# test_2620.net
KiCad netlist of a schematic drawn in EAGLE
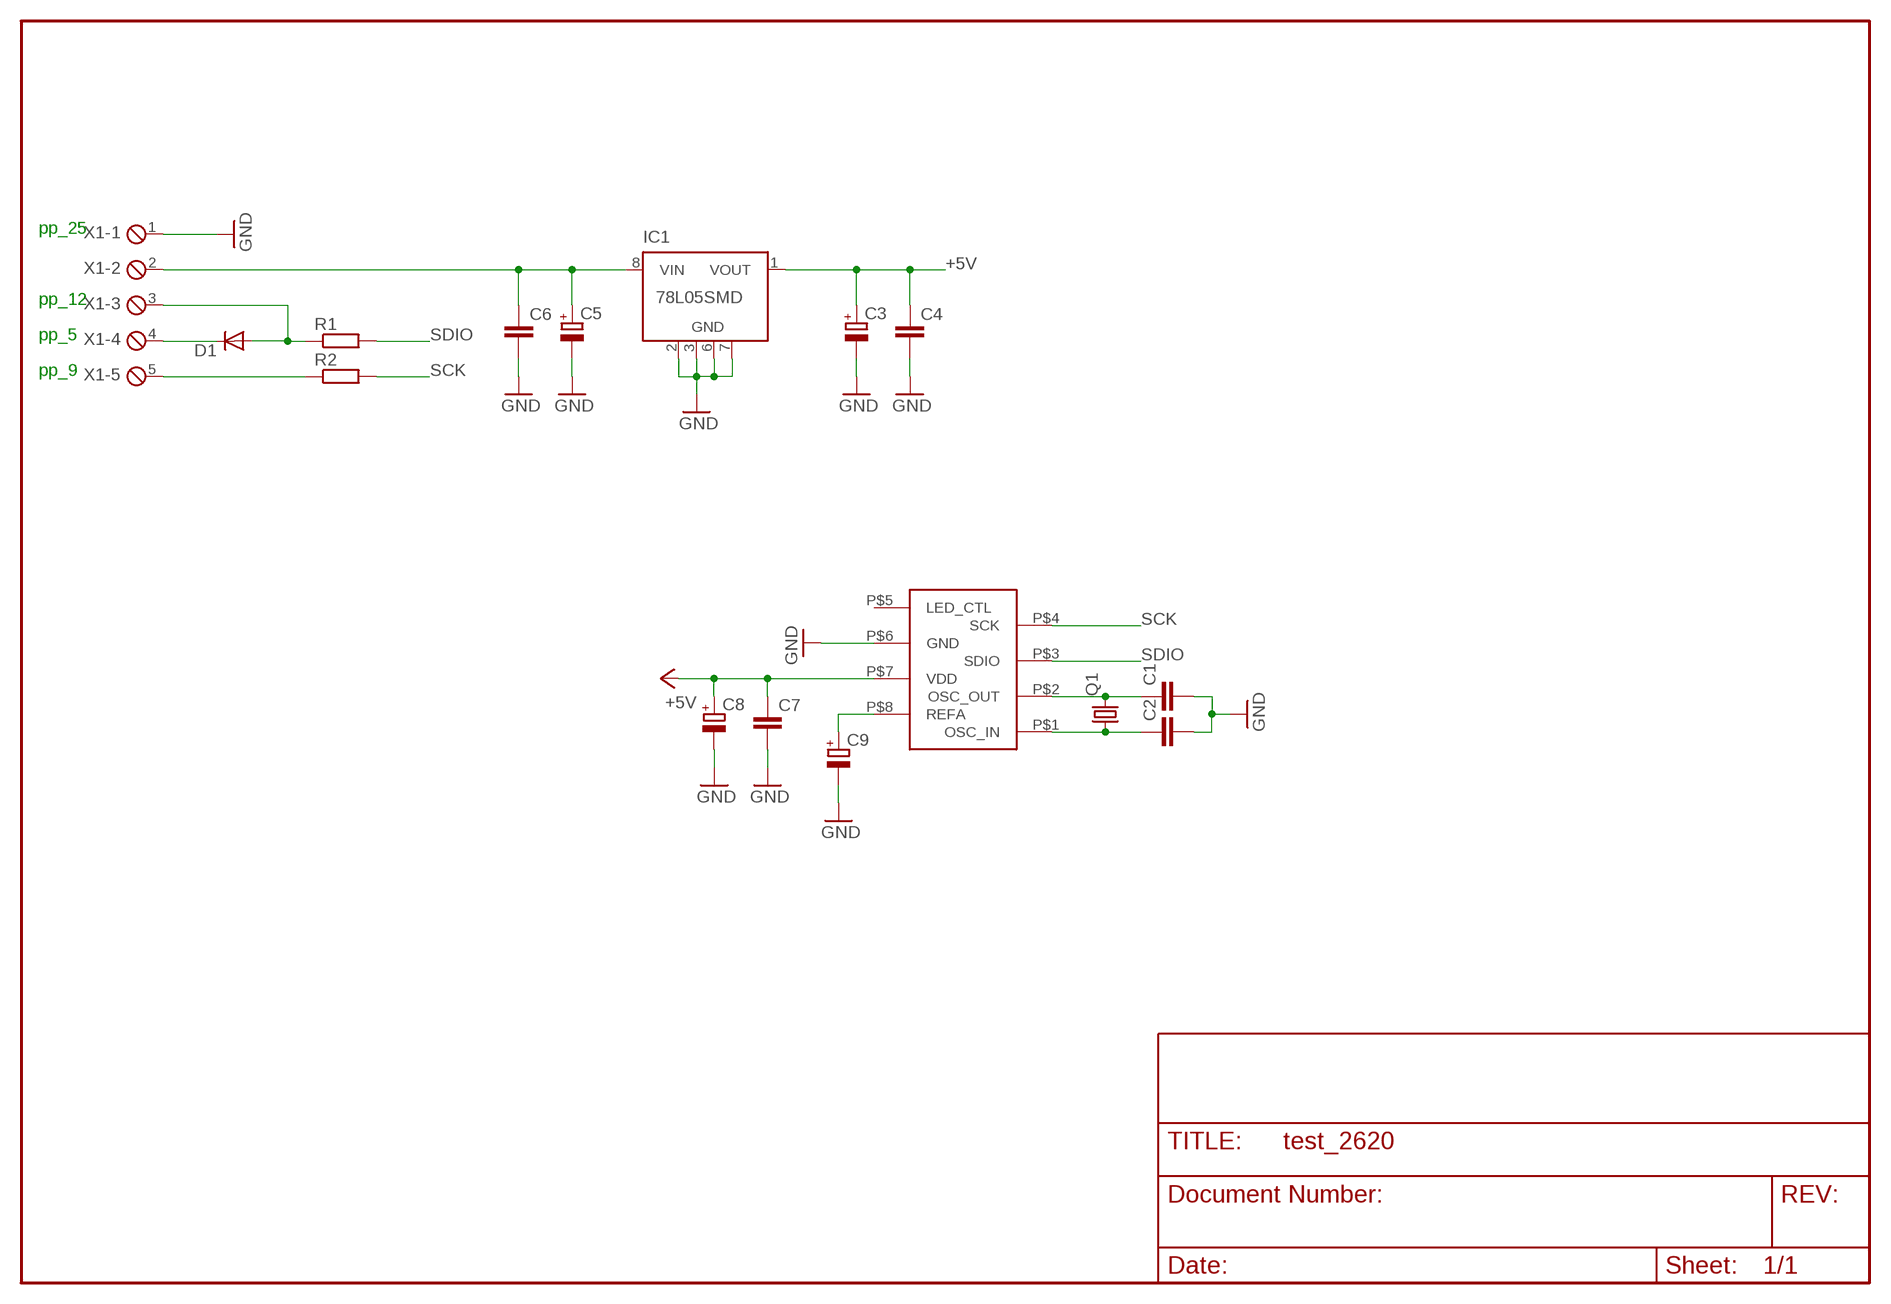
[diagram p0: schematic, sheet 1]

(export (version "E")
  (design (tool "Eeschema 10.0.6"))
  (components
    (comp (ref "C1")
      (value "C-EUC0805K")
      (footprint "eagle-import:C0805K")
      (libsource (lib "eagle-import") (part "C-EUC0805K"))
    )
    (comp (ref "C2")
      (value "C-EUC0805K")
      (footprint "eagle-import:C0805K")
      (libsource (lib "eagle-import") (part "C-EUC0805K"))
    )
    (comp (ref "C3")
      (value "CPOL-EUSMCC")
      (footprint "eagle-import:SMC_C")
      (libsource (lib "eagle-import") (part "CPOL-EUSMCC"))
    )
    (comp (ref "C4")
      (value "C-EUC0805K")
      (footprint "eagle-import:C0805K")
      (libsource (lib "eagle-import") (part "C-EUC0805K"))
    )
    (comp (ref "C5")
      (value "CPOL-EUSMCC")
      (footprint "eagle-import:SMC_C")
      (libsource (lib "eagle-import") (part "CPOL-EUSMCC"))
    )
    (comp (ref "C6")
      (value "C-EUC0805K")
      (footprint "eagle-import:C0805K")
      (libsource (lib "eagle-import") (part "C-EUC0805K"))
    )
    (comp (ref "C7")
      (value "C-EUC0805K")
      (footprint "eagle-import:C0805K")
      (libsource (lib "eagle-import") (part "C-EUC0805K"))
    )
    (comp (ref "C8")
      (value "CPOL-EUSMCC")
      (footprint "eagle-import:SMC_C")
      (libsource (lib "eagle-import") (part "CPOL-EUSMCC"))
    )
    (comp (ref "C9")
      (value "CPOL-EUSMCC")
      (footprint "eagle-import:SMC_C")
      (libsource (lib "eagle-import") (part "CPOL-EUSMCC"))
    )
    (comp (ref "D1")
      (value "DIODE-MINIMELF")
      (footprint "eagle-import:MINIMELF")
      (libsource (lib "eagle-import") (part "DIODE-MINIMELF"))
    )
    (comp (ref "IC1")
      (value "78L05SMD")
      (footprint "eagle-import:SO08")
      (libsource (lib "eagle-import") (part "78LSMD05"))
    )
    (comp (ref "Q1")
      (value "CRYTALHC49U-V")
      (footprint "eagle-import:HC49U-V")
      (libsource (lib "eagle-import") (part "CRYTALHC49U-V"))
    )
    (comp (ref "R1")
      (value "R-EU_R0805")
      (footprint "eagle-import:R0805")
      (libsource (lib "eagle-import") (part "R-EU_R0805"))
    )
    (comp (ref "R2")
      (value "R-EU_R0805")
      (footprint "eagle-import:R0805")
      (libsource (lib "eagle-import") (part "R-EU_R0805"))
    )
    (comp (ref "U$1")
      (value "ADNS2620")
      (footprint "eagle-import:ADNS2620")
      (libsource (lib "eagle-import") (part "ADNS2620"))
    )
    (comp (ref "X1")
      (value "MPT5")
      (footprint "eagle-import:5POL254")
      (libsource (lib "eagle-import") (part "MPT5"))
    )
  )
  (nets
    (net (code "1") (name "+5V") (class "Default")
      (node (ref "C3") (pin "+") (pinfunction "+_+") (pintype "passive"))
      (node (ref "C4") (pin "1") (pinfunction "1_1") (pintype "passive"))
      (node (ref "C7") (pin "1") (pinfunction "1_1") (pintype "passive"))
      (node (ref "C8") (pin "+") (pinfunction "+_+") (pintype "passive"))
      (node (ref "IC1") (pin "1") (pinfunction "VOUT_1") (pintype "output"))
      (node (ref "U$1") (pin "P$7") (pinfunction "VDD_P$7") (pintype "bidirectional"))
    )
    (net (code "2") (name "/SCK") (class "Default")
      (node (ref "R2") (pin "2") (pinfunction "2_2") (pintype "passive"))
      (node (ref "U$1") (pin "P$4") (pinfunction "SCK_P$4") (pintype "bidirectional"))
    )
    (net (code "3") (name "/SDIO") (class "Default")
      (node (ref "R1") (pin "2") (pinfunction "2_2") (pintype "passive"))
      (node (ref "U$1") (pin "P$3") (pinfunction "SDIO_P$3") (pintype "bidirectional"))
    )
    (net (code "4") (name "GND") (class "Default")
      (node (ref "C1") (pin "2") (pinfunction "2_2") (pintype "passive"))
      (node (ref "C2") (pin "2") (pinfunction "2_2") (pintype "passive"))
      (node (ref "C3") (pin "-") (pinfunction "-_-") (pintype "passive"))
      (node (ref "C4") (pin "2") (pinfunction "2_2") (pintype "passive"))
      (node (ref "C5") (pin "-") (pinfunction "-_-") (pintype "passive"))
      (node (ref "C6") (pin "2") (pinfunction "2_2") (pintype "passive"))
      (node (ref "C7") (pin "2") (pinfunction "2_2") (pintype "passive"))
      (node (ref "C8") (pin "-") (pinfunction "-_-") (pintype "passive"))
      (node (ref "C9") (pin "-") (pinfunction "-_-") (pintype "passive"))
      (node (ref "IC1") (pin "2") (pinfunction "GND_2") (pintype "power_in"))
      (node (ref "IC1") (pin "3") (pinfunction "GND_3") (pintype "power_in"))
      (node (ref "IC1") (pin "6") (pinfunction "GND_6") (pintype "power_in"))
      (node (ref "IC1") (pin "7") (pinfunction "GND_7") (pintype "power_in"))
      (node (ref "U$1") (pin "P$6") (pinfunction "GND_P$6") (pintype "bidirectional"))
      (node (ref "X1") (pin "1") (pinfunction "1_1") (pintype "passive"))
    )
    (net (code "5") (name "Net-(IC1A-VIN)") (class "Default")
      (node (ref "C5") (pin "+") (pinfunction "+_+") (pintype "passive"))
      (node (ref "C6") (pin "1") (pinfunction "1_1") (pintype "passive"))
      (node (ref "IC1") (pin "8") (pinfunction "VIN_8") (pintype "passive"))
      (node (ref "X1") (pin "2") (pinfunction "1_2") (pintype "passive"))
    )
    (net (code "6") (name "Net-(U$1-OSC_IN)") (class "Default")
      (node (ref "C2") (pin "1") (pinfunction "1_1") (pintype "passive"))
      (node (ref "Q1") (pin "1") (pinfunction "1_1") (pintype "passive"))
      (node (ref "U$1") (pin "P$1") (pinfunction "OSC_IN_P$1") (pintype "bidirectional"))
    )
    (net (code "7") (name "Net-(U$1-OSC_OUT)") (class "Default")
      (node (ref "C1") (pin "1") (pinfunction "1_1") (pintype "passive"))
      (node (ref "Q1") (pin "2") (pinfunction "2_2") (pintype "passive"))
      (node (ref "U$1") (pin "P$2") (pinfunction "OSC_OUT_P$2") (pintype "bidirectional"))
    )
    (net (code "8") (name "Net-(U$1-REFA)") (class "Default")
      (node (ref "C9") (pin "+") (pinfunction "+_+") (pintype "passive"))
      (node (ref "U$1") (pin "P$8") (pinfunction "REFA_P$8") (pintype "bidirectional"))
    )
    (net (code "9") (name "Net-(X1C-1)") (class "Default")
      (node (ref "D1") (pin "A") (pinfunction "A_A") (pintype "passive"))
      (node (ref "R1") (pin "1") (pinfunction "1_1") (pintype "passive"))
      (node (ref "X1") (pin "3") (pinfunction "1_3") (pintype "passive"))
    )
    (net (code "10") (name "Net-(X1D-1)") (class "Default")
      (node (ref "D1") (pin "C") (pinfunction "C_C") (pintype "passive"))
      (node (ref "X1") (pin "4") (pinfunction "1_4") (pintype "passive"))
    )
    (net (code "11") (name "Net-(X1E-1)") (class "Default")
      (node (ref "R2") (pin "1") (pinfunction "1_1") (pintype "passive"))
      (node (ref "X1") (pin "5") (pinfunction "1_5") (pintype "passive"))
    )
    (net (code "12") (name "unconnected-(U$1-LED_CTL-PadP$5)") (class "Default")
      (node (ref "U$1") (pin "P$5") (pinfunction "LED_CTL_P$5") (pintype "bidirectional"))
    )
  )
)
